# mDotBreakout.net
KiCad netlist of a schematic drawn in EAGLE
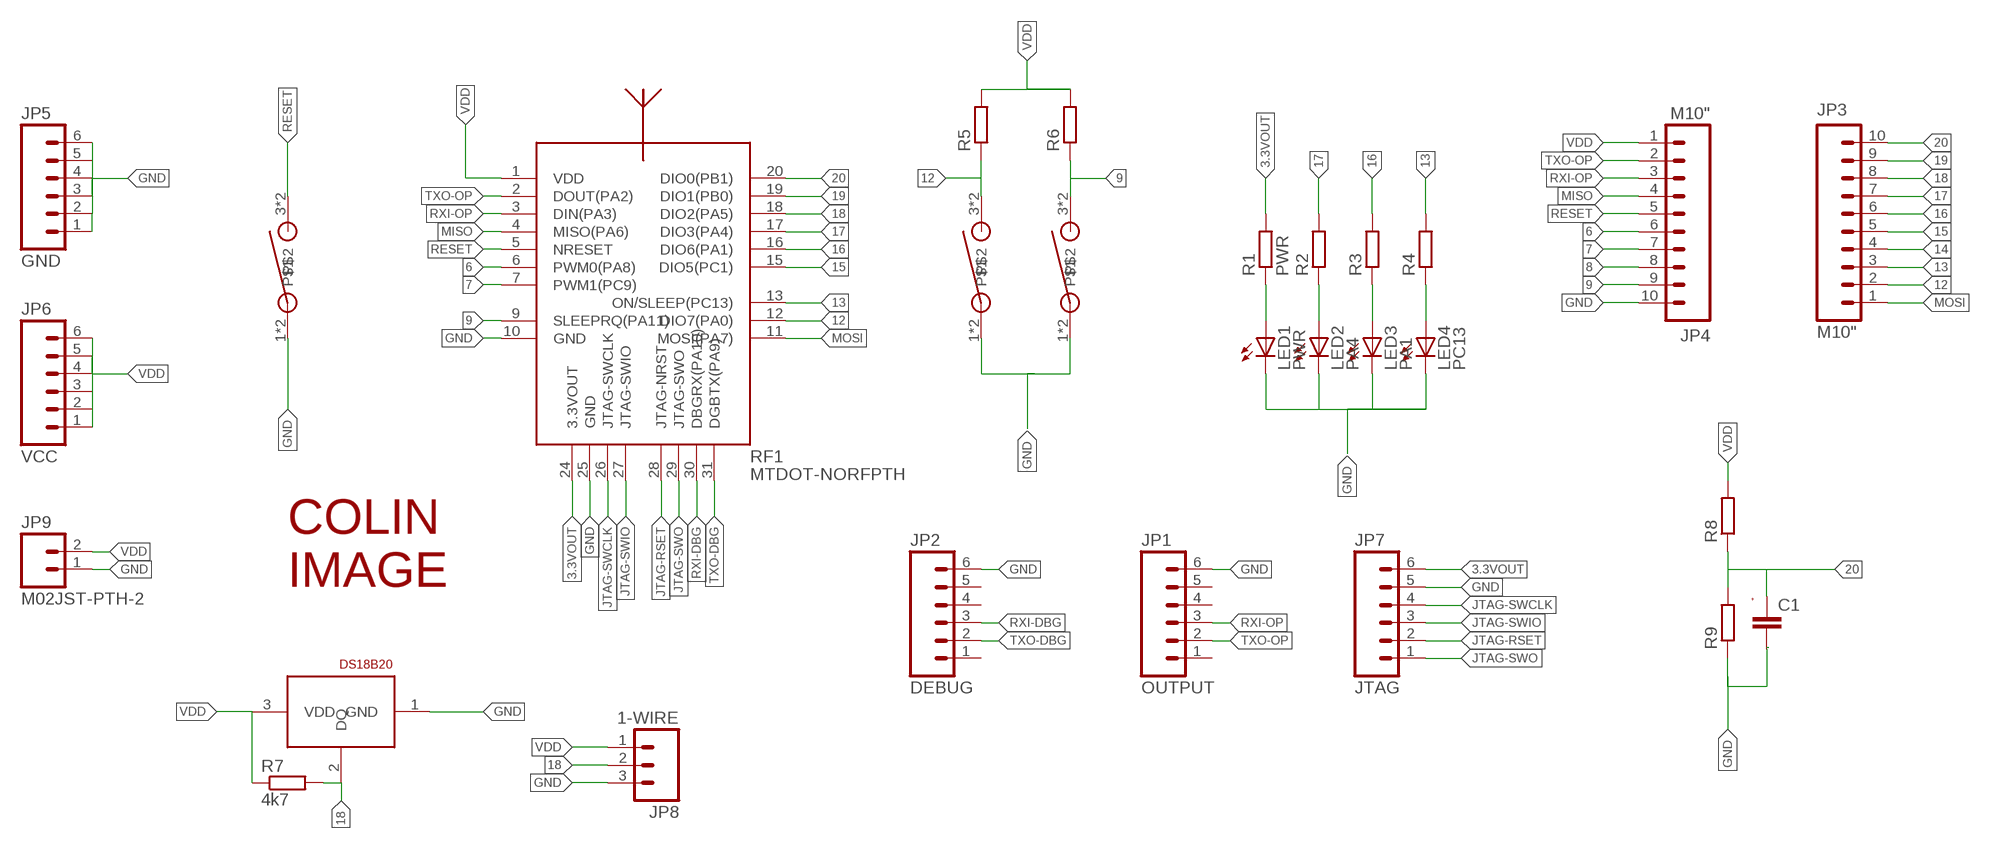
[diagram p0: schematic, sheet 1]

(export (version "E")
  (design (tool "Eeschema 10.0.6"))
  (components
    (comp (ref "C1")
      (value "C-EUC0805K")
      (footprint "eagle-import:C0805K")
      (libsource (lib "eagle-import") (part "C-EUC0805K"))
    )
    (comp (ref "JP1")
      (value "OUTPUT")
      (footprint "eagle-import:1X06")
      (libsource (lib "eagle-import") (part "M06SIP"))
    )
    (comp (ref "JP2")
      (value "DEBUG")
      (footprint "eagle-import:1X06")
      (libsource (lib "eagle-import") (part "M06SIP"))
    )
    (comp (ref "JP3")
      (value "M10\"")
      (footprint "eagle-import:1X10")
      (libsource (lib "eagle-import") (part "M10{dblquote}"))
    )
    (comp (ref "JP4")
      (value "M10\"")
      (footprint "eagle-import:1X10")
      (libsource (lib "eagle-import") (part "M10{dblquote}"))
    )
    (comp (ref "JP5")
      (value "GND")
      (footprint "eagle-import:1X06")
      (libsource (lib "eagle-import") (part "M06SIP"))
    )
    (comp (ref "JP6")
      (value "VCC")
      (footprint "eagle-import:1X06")
      (libsource (lib "eagle-import") (part "M06SIP"))
    )
    (comp (ref "JP7")
      (value "JTAG")
      (footprint "eagle-import:1X06")
      (libsource (lib "eagle-import") (part "M06SIP"))
    )
    (comp (ref "JP8")
      (value "1-WIRE")
      (footprint "eagle-import:JST-3-PTH")
      (libsource (lib "eagle-import") (part "M03JST-PTH"))
    )
    (comp (ref "JP9")
      (value "M02JST-PTH-2")
      (footprint "eagle-import:JST-2-PTH")
      (libsource (lib "eagle-import") (part "M02JST-PTH-2"))
    )
    (comp (ref "LED1")
      (value "PWR")
      (footprint "eagle-import:CHIPLED_0805")
      (libsource (lib "eagle-import") (part "LEDCHIPLED_0805"))
    )
    (comp (ref "LED2")
      (value "PA4")
      (footprint "eagle-import:CHIPLED_0805")
      (libsource (lib "eagle-import") (part "LEDCHIPLED_0805"))
    )
    (comp (ref "LED3")
      (value "PA1")
      (footprint "eagle-import:CHIPLED_0805")
      (libsource (lib "eagle-import") (part "LEDCHIPLED_0805"))
    )
    (comp (ref "LED4")
      (value "PC13")
      (footprint "eagle-import:CHIPLED_0805")
      (libsource (lib "eagle-import") (part "LEDCHIPLED_0805"))
    )
    (comp (ref "R1")
      (value "PWR")
      (footprint "eagle-import:R0805")
      (libsource (lib "eagle-import") (part "R-EUR0805"))
    )
    (comp (ref "R2")
      (value "R-EUR0805")
      (footprint "eagle-import:R0805")
      (libsource (lib "eagle-import") (part "R-EUR0805"))
    )
    (comp (ref "R3")
      (value "R-EUR0805")
      (footprint "eagle-import:R0805")
      (libsource (lib "eagle-import") (part "R-EUR0805"))
    )
    (comp (ref "R4")
      (value "R-EUR0805")
      (footprint "eagle-import:R0805")
      (libsource (lib "eagle-import") (part "R-EUR0805"))
    )
    (comp (ref "R5")
      (value "R-EUR0805")
      (footprint "eagle-import:R0805")
      (libsource (lib "eagle-import") (part "R-EUR0805"))
    )
    (comp (ref "R6")
      (value "R-EUR0805")
      (footprint "eagle-import:R0805")
      (libsource (lib "eagle-import") (part "R-EUR0805"))
    )
    (comp (ref "R7")
      (value "4k7")
      (footprint "eagle-import:R0805")
      (libsource (lib "eagle-import") (part "R-EUR0805"))
    )
    (comp (ref "R8")
      (value "R-EUR0805")
      (footprint "eagle-import:R0805")
      (libsource (lib "eagle-import") (part "R-EUR0805"))
    )
    (comp (ref "R9")
      (value "R-EUR0805")
      (footprint "eagle-import:R0805")
      (libsource (lib "eagle-import") (part "R-EUR0805"))
    )
    (comp (ref "RF1")
      (value "MTDOT-NORFPTH")
      (footprint "eagle-import:MTDOT-M1-TRC-PTH-NORF")
      (libsource (lib "eagle-import") (part "MTDOT-NORFPTH"))
    )
    (comp (ref "RST")
      (value "SWITCH_SPSTPTS645_SMT")
      (footprint "eagle-import:PTS645_SMT")
      (libsource (lib "eagle-import") (part "SWITCH_SPSTPTS645_SMT"))
    )
    (comp (ref "U$2")
      (value "SWITCH_SPSTPTS645_SMT")
      (footprint "eagle-import:PTS645_SMT")
      (libsource (lib "eagle-import") (part "SWITCH_SPSTPTS645_SMT"))
    )
    (comp (ref "U$3")
      (value "SWITCH_SPSTPTS645_SMT")
      (footprint "eagle-import:PTS645_SMT")
      (libsource (lib "eagle-import") (part "SWITCH_SPSTPTS645_SMT"))
    )
    (comp (ref "U$4")
      (value "DS18B20TO92")
      (footprint "eagle-import:TO92")
      (libsource (lib "eagle-import") (part "DS18B20TO92"))
    )
    (comp (ref "U$5")
      (value "COLIN")
      (footprint "eagle-import:COLIN")
      (libsource (lib "eagle-import") (part "COLIN"))
    )
  )
  (nets
    (net (code "1") (name "3.3VOUT") (class "Default")
      (node (ref "JP7") (pin "6") (pinfunction "6_6") (pintype "passive"))
      (node (ref "R1") (pin "2") (pinfunction "2_2") (pintype "passive"))
      (node (ref "RF1") (pin "24") (pinfunction "3.3VOUT_24") (pintype "power_in"))
    )
    (net (code "2") (name "6") (class "Default")
      (node (ref "JP4") (pin "6") (pinfunction "6_6") (pintype "passive"))
      (node (ref "RF1") (pin "6") (pinfunction "PWM0(PA8)_6") (pintype "bidirectional"))
    )
    (net (code "3") (name "7") (class "Default")
      (node (ref "JP4") (pin "7") (pinfunction "7_7") (pintype "passive"))
      (node (ref "RF1") (pin "7") (pinfunction "PWM1(PC9)_7") (pintype "bidirectional"))
    )
    (net (code "4") (name "8") (class "Default")
      (node (ref "JP4") (pin "8") (pinfunction "8_8") (pintype "passive"))
    )
    (net (code "5") (name "9") (class "Default")
      (node (ref "JP4") (pin "9") (pinfunction "9_9") (pintype "passive"))
      (node (ref "R6") (pin "1") (pinfunction "1_1") (pintype "passive"))
      (node (ref "RF1") (pin "9") (pinfunction "SLEEPRQ(PA11)_9") (pintype "bidirectional"))
      (node (ref "U$3") (pin "3") (pinfunction "P$2_3") (pintype "bidirectional"))
      (node (ref "U$3") (pin "4") (pinfunction "P$2_4") (pintype "bidirectional"))
    )
    (net (code "6") (name "12") (class "Default")
      (node (ref "JP3") (pin "2") (pinfunction "2_2") (pintype "passive"))
      (node (ref "R5") (pin "1") (pinfunction "1_1") (pintype "passive"))
      (node (ref "RF1") (pin "12") (pinfunction "DIO7(PA0)_12") (pintype "bidirectional"))
      (node (ref "U$2") (pin "3") (pinfunction "P$2_3") (pintype "bidirectional"))
      (node (ref "U$2") (pin "4") (pinfunction "P$2_4") (pintype "bidirectional"))
    )
    (net (code "7") (name "13") (class "Default")
      (node (ref "JP3") (pin "3") (pinfunction "3_3") (pintype "passive"))
      (node (ref "R4") (pin "2") (pinfunction "2_2") (pintype "passive"))
      (node (ref "RF1") (pin "13") (pinfunction "ON/SLEEP(PC13)_13") (pintype "bidirectional"))
    )
    (net (code "8") (name "14") (class "Default")
      (node (ref "JP3") (pin "4") (pinfunction "4_4") (pintype "passive"))
    )
    (net (code "9") (name "15") (class "Default")
      (node (ref "JP3") (pin "5") (pinfunction "5_5") (pintype "passive"))
      (node (ref "RF1") (pin "15") (pinfunction "DIO5(PC1)_15") (pintype "bidirectional"))
    )
    (net (code "10") (name "16") (class "Default")
      (node (ref "JP3") (pin "6") (pinfunction "6_6") (pintype "passive"))
      (node (ref "R3") (pin "2") (pinfunction "2_2") (pintype "passive"))
      (node (ref "RF1") (pin "16") (pinfunction "DIO6(PA1)_16") (pintype "bidirectional"))
    )
    (net (code "11") (name "17") (class "Default")
      (node (ref "JP3") (pin "7") (pinfunction "7_7") (pintype "passive"))
      (node (ref "R2") (pin "2") (pinfunction "2_2") (pintype "passive"))
      (node (ref "RF1") (pin "17") (pinfunction "DIO3(PA4)_17") (pintype "bidirectional"))
    )
    (net (code "12") (name "18") (class "Default")
      (node (ref "JP3") (pin "8") (pinfunction "8_8") (pintype "passive"))
      (node (ref "JP8") (pin "2") (pinfunction "2_2") (pintype "passive"))
      (node (ref "R7") (pin "2") (pinfunction "2_2") (pintype "passive"))
      (node (ref "RF1") (pin "18") (pinfunction "DIO2(PA5)_18") (pintype "bidirectional"))
      (node (ref "U$4") (pin "2") (pinfunction "DQ_2") (pintype "bidirectional"))
    )
    (net (code "13") (name "19") (class "Default")
      (node (ref "JP3") (pin "9") (pinfunction "9_9") (pintype "passive"))
      (node (ref "RF1") (pin "19") (pinfunction "DIO1(PB0)_19") (pintype "bidirectional"))
    )
    (net (code "14") (name "20") (class "Default")
      (node (ref "C1") (pin "1") (pinfunction "1_1") (pintype "passive"))
      (node (ref "JP3") (pin "10") (pinfunction "10_10") (pintype "passive"))
      (node (ref "R8") (pin "1") (pinfunction "1_1") (pintype "passive"))
      (node (ref "R9") (pin "2") (pinfunction "2_2") (pintype "passive"))
      (node (ref "RF1") (pin "20") (pinfunction "DIO0(PB1)_20") (pintype "bidirectional"))
    )
    (net (code "15") (name "GND") (class "Default")
      (node (ref "C1") (pin "2") (pinfunction "2_2") (pintype "passive"))
      (node (ref "JP1") (pin "6") (pinfunction "6_6") (pintype "passive"))
      (node (ref "JP2") (pin "6") (pinfunction "6_6") (pintype "passive"))
      (node (ref "JP4") (pin "10") (pinfunction "10_10") (pintype "passive"))
      (node (ref "JP5") (pin "1") (pinfunction "1_1") (pintype "passive"))
      (node (ref "JP5") (pin "2") (pinfunction "2_2") (pintype "passive"))
      (node (ref "JP5") (pin "3") (pinfunction "3_3") (pintype "passive"))
      (node (ref "JP5") (pin "4") (pinfunction "4_4") (pintype "passive"))
      (node (ref "JP5") (pin "5") (pinfunction "5_5") (pintype "passive"))
      (node (ref "JP5") (pin "6") (pinfunction "6_6") (pintype "passive"))
      (node (ref "JP7") (pin "5") (pinfunction "5_5") (pintype "passive"))
      (node (ref "JP8") (pin "3") (pinfunction "3_3") (pintype "passive"))
      (node (ref "JP9") (pin "1") (pinfunction "1_1") (pintype "passive"))
      (node (ref "LED1") (pin "C") (pinfunction "C_C") (pintype "passive"))
      (node (ref "LED2") (pin "C") (pinfunction "C_C") (pintype "passive"))
      (node (ref "LED3") (pin "C") (pinfunction "C_C") (pintype "passive"))
      (node (ref "LED4") (pin "C") (pinfunction "C_C") (pintype "passive"))
      (node (ref "R9") (pin "1") (pinfunction "1_1") (pintype "passive"))
      (node (ref "RF1") (pin "10") (pinfunction "GND_10") (pintype "power_in"))
      (node (ref "RF1") (pin "25") (pinfunction "GND_25") (pintype "power_in"))
      (node (ref "RST") (pin "1") (pinfunction "P$1_1") (pintype "bidirectional"))
      (node (ref "RST") (pin "2") (pinfunction "P$1_2") (pintype "bidirectional"))
      (node (ref "U$2") (pin "1") (pinfunction "P$1_1") (pintype "bidirectional"))
      (node (ref "U$2") (pin "2") (pinfunction "P$1_2") (pintype "bidirectional"))
      (node (ref "U$3") (pin "1") (pinfunction "P$1_1") (pintype "bidirectional"))
      (node (ref "U$3") (pin "2") (pinfunction "P$1_2") (pintype "bidirectional"))
      (node (ref "U$4") (pin "1") (pinfunction "GND_1") (pintype "power_in"))
    )
    (net (code "16") (name "JTAG-RSET") (class "Default")
      (node (ref "JP7") (pin "2") (pinfunction "2_2") (pintype "passive"))
      (node (ref "RF1") (pin "28") (pinfunction "JTAG-NRST_28") (pintype "bidirectional"))
    )
    (net (code "17") (name "JTAG-SWCLK") (class "Default")
      (node (ref "JP7") (pin "4") (pinfunction "4_4") (pintype "passive"))
      (node (ref "RF1") (pin "26") (pinfunction "JTAG-SWCLK_26") (pintype "bidirectional"))
    )
    (net (code "18") (name "JTAG-SWIO") (class "Default")
      (node (ref "JP7") (pin "3") (pinfunction "3_3") (pintype "passive"))
      (node (ref "RF1") (pin "27") (pinfunction "JTAG-SWIO_27") (pintype "bidirectional"))
    )
    (net (code "19") (name "JTAG-SWO") (class "Default")
      (node (ref "JP7") (pin "1") (pinfunction "1_1") (pintype "passive"))
      (node (ref "RF1") (pin "29") (pinfunction "JTAG-SWO_29") (pintype "bidirectional"))
    )
    (net (code "20") (name "MISO") (class "Default")
      (node (ref "JP4") (pin "4") (pinfunction "4_4") (pintype "passive"))
      (node (ref "RF1") (pin "4") (pinfunction "MISO(PA6)_4") (pintype "bidirectional"))
    )
    (net (code "21") (name "MOSI") (class "Default")
      (node (ref "JP3") (pin "1") (pinfunction "1_1") (pintype "passive"))
      (node (ref "RF1") (pin "11") (pinfunction "MOSI(PA7)_11") (pintype "bidirectional"))
    )
    (net (code "22") (name "Net-(LED1-PadA)") (class "Default")
      (node (ref "LED1") (pin "A") (pinfunction "A_A") (pintype "passive"))
      (node (ref "R1") (pin "1") (pinfunction "1_1") (pintype "passive"))
    )
    (net (code "23") (name "Net-(LED2-PadA)") (class "Default")
      (node (ref "LED2") (pin "A") (pinfunction "A_A") (pintype "passive"))
      (node (ref "R2") (pin "1") (pinfunction "1_1") (pintype "passive"))
    )
    (net (code "24") (name "Net-(LED3-PadA)") (class "Default")
      (node (ref "LED3") (pin "A") (pinfunction "A_A") (pintype "passive"))
      (node (ref "R3") (pin "1") (pinfunction "1_1") (pintype "passive"))
    )
    (net (code "25") (name "Net-(LED4-PadA)") (class "Default")
      (node (ref "LED4") (pin "A") (pinfunction "A_A") (pintype "passive"))
      (node (ref "R4") (pin "1") (pinfunction "1_1") (pintype "passive"))
    )
    (net (code "26") (name "RESET") (class "Default")
      (node (ref "JP4") (pin "5") (pinfunction "5_5") (pintype "passive"))
      (node (ref "RF1") (pin "5") (pinfunction "NRESET_5") (pintype "bidirectional"))
      (node (ref "RST") (pin "3") (pinfunction "P$2_3") (pintype "bidirectional"))
      (node (ref "RST") (pin "4") (pinfunction "P$2_4") (pintype "bidirectional"))
    )
    (net (code "27") (name "RXI-DBG") (class "Default")
      (node (ref "JP2") (pin "3") (pinfunction "3_3") (pintype "passive"))
      (node (ref "RF1") (pin "30") (pinfunction "DBGRX(PA10)_30") (pintype "bidirectional"))
    )
    (net (code "28") (name "RXI-OP") (class "Default")
      (node (ref "JP1") (pin "3") (pinfunction "3_3") (pintype "passive"))
      (node (ref "JP4") (pin "3") (pinfunction "3_3") (pintype "passive"))
      (node (ref "RF1") (pin "3") (pinfunction "DIN(PA3)_3") (pintype "bidirectional"))
    )
    (net (code "29") (name "TXO-DBG") (class "Default")
      (node (ref "JP2") (pin "2") (pinfunction "2_2") (pintype "passive"))
      (node (ref "RF1") (pin "31") (pinfunction "DGBTX(PA9)_31") (pintype "bidirectional"))
    )
    (net (code "30") (name "TXO-OP") (class "Default")
      (node (ref "JP1") (pin "2") (pinfunction "2_2") (pintype "passive"))
      (node (ref "JP4") (pin "2") (pinfunction "2_2") (pintype "passive"))
      (node (ref "RF1") (pin "2") (pinfunction "DOUT(PA2)_2") (pintype "bidirectional"))
    )
    (net (code "31") (name "VDD") (class "Default")
      (node (ref "JP4") (pin "1") (pinfunction "1_1") (pintype "passive"))
      (node (ref "JP6") (pin "1") (pinfunction "1_1") (pintype "passive"))
      (node (ref "JP6") (pin "2") (pinfunction "2_2") (pintype "passive"))
      (node (ref "JP6") (pin "3") (pinfunction "3_3") (pintype "passive"))
      (node (ref "JP6") (pin "4") (pinfunction "4_4") (pintype "passive"))
      (node (ref "JP6") (pin "5") (pinfunction "5_5") (pintype "passive"))
      (node (ref "JP6") (pin "6") (pinfunction "6_6") (pintype "passive"))
      (node (ref "JP8") (pin "1") (pinfunction "1_1") (pintype "passive"))
      (node (ref "JP9") (pin "2") (pinfunction "2_2") (pintype "passive"))
      (node (ref "R5") (pin "2") (pinfunction "2_2") (pintype "passive"))
      (node (ref "R6") (pin "2") (pinfunction "2_2") (pintype "passive"))
      (node (ref "R7") (pin "1") (pinfunction "1_1") (pintype "passive"))
      (node (ref "R8") (pin "2") (pinfunction "2_2") (pintype "passive"))
      (node (ref "RF1") (pin "1") (pinfunction "VDD_1") (pintype "power_in"))
      (node (ref "U$4") (pin "3") (pinfunction "VDD_3") (pintype "power_in"))
    )
    (net (code "32") (name "unconnected-(JP1-Pad1)") (class "Default")
      (node (ref "JP1") (pin "1") (pinfunction "1_1") (pintype "passive"))
    )
    (net (code "33") (name "unconnected-(JP1-Pad4)") (class "Default")
      (node (ref "JP1") (pin "4") (pinfunction "4_4") (pintype "passive"))
    )
    (net (code "34") (name "unconnected-(JP1-Pad5)") (class "Default")
      (node (ref "JP1") (pin "5") (pinfunction "5_5") (pintype "passive"))
    )
    (net (code "35") (name "unconnected-(JP2-Pad1)") (class "Default")
      (node (ref "JP2") (pin "1") (pinfunction "1_1") (pintype "passive"))
    )
    (net (code "36") (name "unconnected-(JP2-Pad4)") (class "Default")
      (node (ref "JP2") (pin "4") (pinfunction "4_4") (pintype "passive"))
    )
    (net (code "37") (name "unconnected-(JP2-Pad5)") (class "Default")
      (node (ref "JP2") (pin "5") (pinfunction "5_5") (pintype "passive"))
    )
  )
)
